# solar_harvester.net
KiCad netlist of a schematic drawn in EAGLE
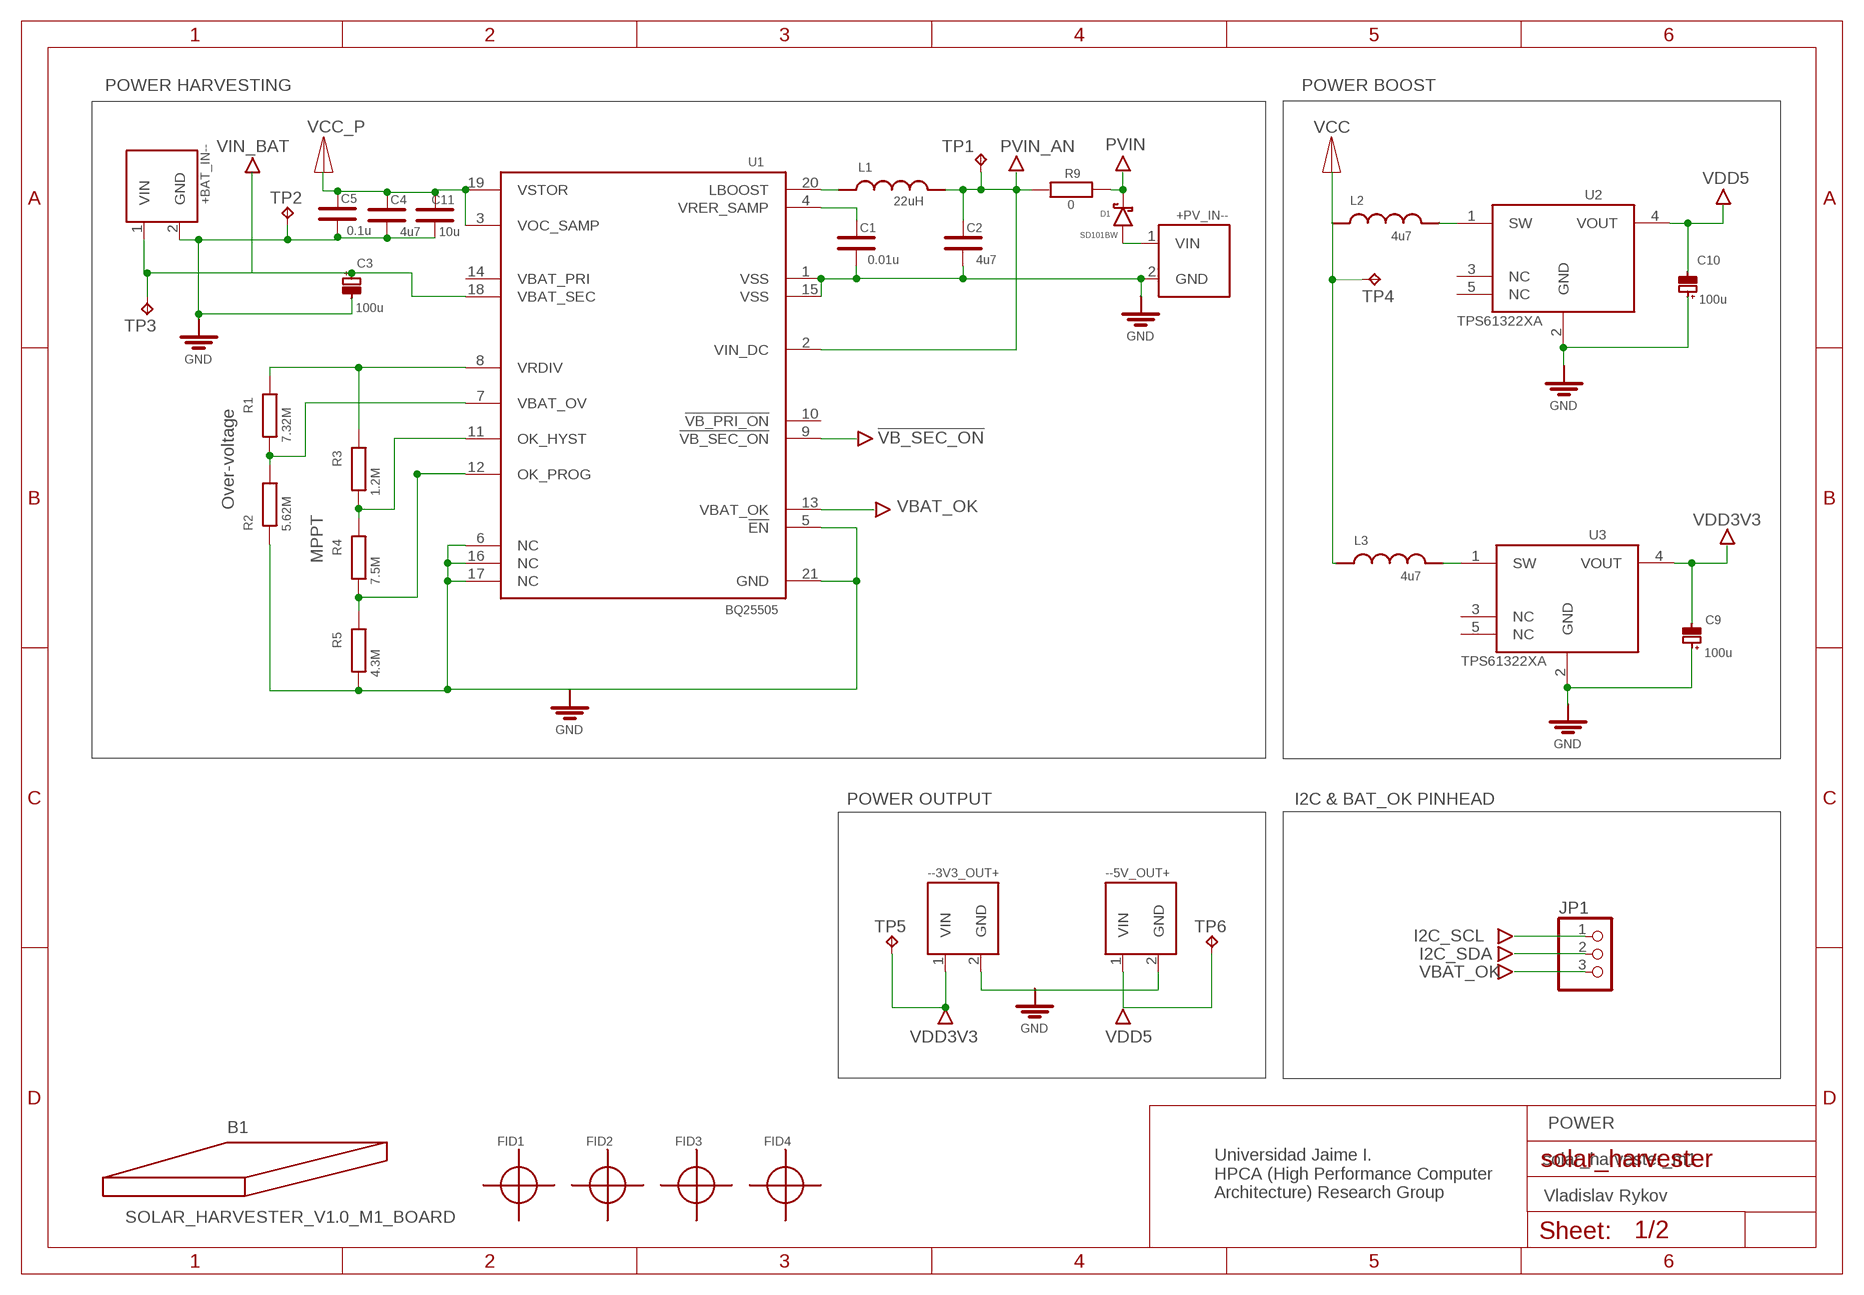
[diagram p0: schematic, sheet 1]
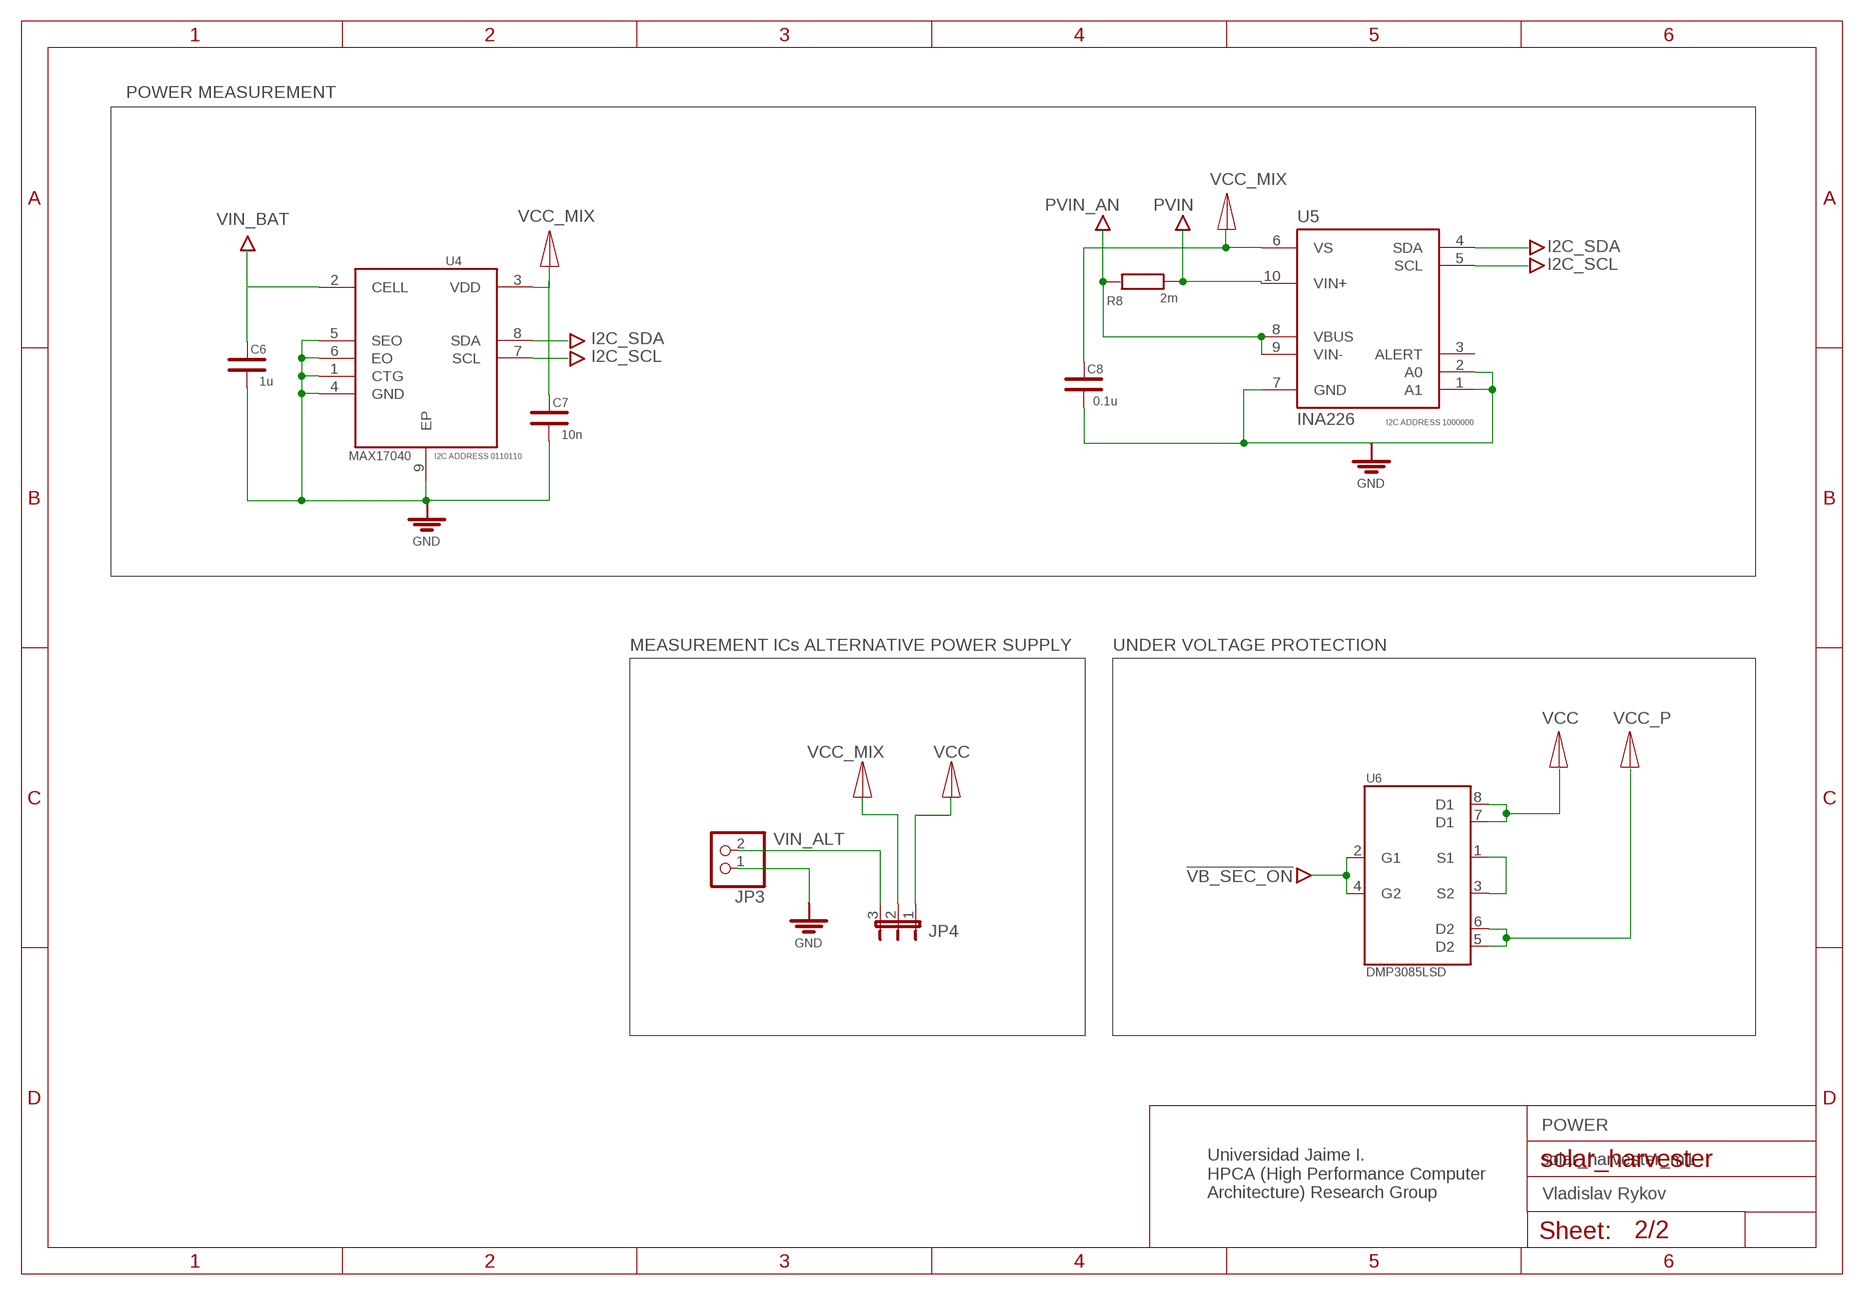
[diagram p1: schematic, sheet 2]

(export (version "E")
  (design (tool "Eeschema 10.0.6"))
  (components
    (comp (ref "C6")
      (value "1u")
      (footprint "eagle-import:1608_FOOTPRINT")
      (libsource (lib "eagle-import") (part "1608_CAP"))
    )
    (comp (ref "C7")
      (value "10n")
      (footprint "eagle-import:1608_FOOTPRINT")
      (libsource (lib "eagle-import") (part "1608_CAP"))
    )
    (comp (ref "C8")
      (value "0.1u")
      (footprint "eagle-import:1608_FOOTPRINT")
      (libsource (lib "eagle-import") (part "1608_CAP"))
    )
    (comp (ref "JP3")
      (value "PINHD-1X2")
      (footprint "eagle-import:1X02")
      (libsource (lib "eagle-import") (part "PINHD-1X2"))
    )
    (comp (ref "JP4")
      (value "JP2E")
      (footprint "eagle-import:JP2")
      (libsource (lib "eagle-import") (part "JP2E"))
    )
    (comp (ref "R8")
      (value "2m")
      (footprint "eagle-import:RESISTOR_2012_FOOTPRINT")
      (libsource (lib "eagle-import") (part "RESISTOR_2012"))
    )
    (comp (ref "U4")
      (value "MAX17040")
      (footprint "eagle-import:MAX17040G+T_FOOTPRINT")
      (libsource (lib "eagle-import") (part "MAX17040"))
    )
    (comp (ref "U5")
      (value "INA226")
      (footprint "eagle-import:INA226_FOOTPRINT")
      (libsource (lib "eagle-import") (part "INA226"))
    )
    (comp (ref "U6")
      (value "DMP3085LSD")
      (footprint "eagle-import:SO-8")
      (libsource (lib "eagle-import") (part "DMP3085LSD"))
    )
    (comp (ref "+BAT_IN--")
      (value "CONN_SCEW_TYPE_2P")
      (footprint "eagle-import:CONN_SCREW_TYPE_2P")
      (libsource (lib "eagle-import") (part "CONN_SCEW_TYPE_2P"))
    )
    (comp (ref "+PV_IN--")
      (value "CONN_SCEW_TYPE_2P")
      (footprint "eagle-import:CONN_SCREW_TYPE_2P")
      (libsource (lib "eagle-import") (part "CONN_SCEW_TYPE_2P"))
    )
    (comp (ref "--3V3_OUT+")
      (value "CONN_SCEW_TYPE_2P")
      (footprint "eagle-import:CONN_SCREW_TYPE_2P")
      (libsource (lib "eagle-import") (part "CONN_SCEW_TYPE_2P"))
    )
    (comp (ref "--5V_OUT+")
      (value "CONN_SCEW_TYPE_2P")
      (footprint "eagle-import:CONN_SCREW_TYPE_2P")
      (libsource (lib "eagle-import") (part "CONN_SCEW_TYPE_2P"))
    )
    (comp (ref "B1")
      (value "SOLAR_HARVESTER_V1.0_M1_BOARD")
      (footprint "eagle-import:SOLAR_HARVESTER_V1.0_M1_FOOTPRINT")
      (libsource (lib "eagle-import") (part "SOLAR_HARVESTER_V1.0_M1_BOARD"))
    )
    (comp (ref "C1")
      (value "0.01u")
      (footprint "eagle-import:1608_FOOTPRINT")
      (libsource (lib "eagle-import") (part "1608_CAP"))
    )
    (comp (ref "C2")
      (value "4u7")
      (footprint "eagle-import:1608_FOOTPRINT")
      (libsource (lib "eagle-import") (part "1608_CAP"))
    )
    (comp (ref "C3")
      (value "100u")
      (footprint "eagle-import:3528_TAN_FOOTPRINT")
      (libsource (lib "eagle-import") (part "3528_POL_CAP"))
    )
    (comp (ref "C4")
      (value "4u7")
      (footprint "eagle-import:1608_FOOTPRINT")
      (libsource (lib "eagle-import") (part "1608_CAP"))
    )
    (comp (ref "C5")
      (value "0.1u")
      (footprint "eagle-import:1608_FOOTPRINT")
      (libsource (lib "eagle-import") (part "1608_CAP"))
    )
    (comp (ref "C9")
      (value "100u")
      (footprint "eagle-import:3528_TAN_FOOTPRINT")
      (libsource (lib "eagle-import") (part "3528_POL_CAP"))
    )
    (comp (ref "C10")
      (value "100u")
      (footprint "eagle-import:3528_TAN_FOOTPRINT")
      (libsource (lib "eagle-import") (part "3528_POL_CAP"))
    )
    (comp (ref "C11")
      (value "10u")
      (footprint "eagle-import:1608_FOOTPRINT")
      (libsource (lib "eagle-import") (part "1608_CAP"))
    )
    (comp (ref "D1")
      (value "SD101BW")
      (footprint "eagle-import:SOD-123")
      (libsource (lib "eagle-import") (part "SD101BW"))
    )
    (comp (ref "FID1")
      (value "FIDUCIAL_25")
      (footprint "eagle-import:FIDUCIAL_25")
      (libsource (lib "eagle-import") (part "FIDUCIAL_25"))
    )
    (comp (ref "FID2")
      (value "FIDUCIAL_25")
      (footprint "eagle-import:FIDUCIAL_25")
      (libsource (lib "eagle-import") (part "FIDUCIAL_25"))
    )
    (comp (ref "FID3")
      (value "FIDUCIAL_25")
      (footprint "eagle-import:FIDUCIAL_25")
      (libsource (lib "eagle-import") (part "FIDUCIAL_25"))
    )
    (comp (ref "FID4")
      (value "FIDUCIAL_25")
      (footprint "eagle-import:FIDUCIAL_25")
      (libsource (lib "eagle-import") (part "FIDUCIAL_25"))
    )
    (comp (ref "JP1")
      (value "PINHD-1X3")
      (footprint "eagle-import:1X03")
      (libsource (lib "eagle-import") (part "PINHD-1X3"))
    )
    (comp (ref "L1")
      (value "22uH")
      (footprint "eagle-import:FIXED_4040_FOOTPRINT")
      (libsource (lib "eagle-import") (part "FIXED_4040"))
    )
    (comp (ref "L2")
      (value "4u7")
      (footprint "eagle-import:FIXED_5050_FOOTPRINT")
      (libsource (lib "eagle-import") (part "FIXED_5050"))
    )
    (comp (ref "L3")
      (value "4u7")
      (footprint "eagle-import:FIXED_2520_FOOTPRINT")
      (libsource (lib "eagle-import") (part "FIXED_2520"))
    )
    (comp (ref "R1")
      (value "7.32M")
      (footprint "eagle-import:RESISTOR_1608_FOOTPRINT")
      (libsource (lib "eagle-import") (part "RESISTOR_1608"))
    )
    (comp (ref "R2")
      (value "5.62M")
      (footprint "eagle-import:RESISTOR_1608_FOOTPRINT")
      (libsource (lib "eagle-import") (part "RESISTOR_1608"))
    )
    (comp (ref "R3")
      (value "1.2M")
      (footprint "eagle-import:RESISTOR_1608_FOOTPRINT")
      (libsource (lib "eagle-import") (part "RESISTOR_1608"))
    )
    (comp (ref "R4")
      (value "7.5M")
      (footprint "eagle-import:RESISTOR_1608_FOOTPRINT")
      (libsource (lib "eagle-import") (part "RESISTOR_1608"))
    )
    (comp (ref "R5")
      (value "4.3M")
      (footprint "eagle-import:RESISTOR_1608_FOOTPRINT")
      (libsource (lib "eagle-import") (part "RESISTOR_1608"))
    )
    (comp (ref "R9")
      (value "0")
      (footprint "eagle-import:RESISTOR_1608_FOOTPRINT")
      (libsource (lib "eagle-import") (part "RESISTOR_1608"))
    )
    (comp (ref "TP1")
      (value "TPTP10SQ")
      (footprint "eagle-import:TP10SQ")
      (libsource (lib "eagle-import") (part "TPTP10SQ"))
    )
    (comp (ref "TP2")
      (value "TPTP10SQ")
      (footprint "eagle-import:TP10SQ")
      (libsource (lib "eagle-import") (part "TPTP10SQ"))
    )
    (comp (ref "TP3")
      (value "TPTP10SQ")
      (footprint "eagle-import:TP10SQ")
      (libsource (lib "eagle-import") (part "TPTP10SQ"))
    )
    (comp (ref "TP4")
      (value "TPTP10SQ")
      (footprint "eagle-import:TP10SQ")
      (libsource (lib "eagle-import") (part "TPTP10SQ"))
    )
    (comp (ref "TP5")
      (value "TPTP10SQ")
      (footprint "eagle-import:TP10SQ")
      (libsource (lib "eagle-import") (part "TPTP10SQ"))
    )
    (comp (ref "TP6")
      (value "TPTP10SQ")
      (footprint "eagle-import:TP10SQ")
      (libsource (lib "eagle-import") (part "TPTP10SQ"))
    )
    (comp (ref "U1")
      (value "BQ25505")
      (footprint "eagle-import:BQ25505_FOOTPRINT")
      (libsource (lib "eagle-import") (part "BQ25505"))
    )
    (comp (ref "U2")
      (value "TPS61322XA")
      (footprint "eagle-import:TPS61322XA_FOOTPRINT")
      (libsource (lib "eagle-import") (part "TPS61322XA"))
    )
    (comp (ref "U3")
      (value "TPS61322XA")
      (footprint "eagle-import:TPS61322XA_FOOTPRINT")
      (libsource (lib "eagle-import") (part "TPS61322XA"))
    )
  )
  (nets
    (net (code "1") (name "GND") (class "Default")
      (node (ref "+BAT_IN--") (pin "2") (pinfunction "GND_2") (pintype "bidirectional"))
      (node (ref "+PV_IN--") (pin "2") (pinfunction "GND_2") (pintype "bidirectional"))
      (node (ref "--3V3_OUT+") (pin "2") (pinfunction "GND_2") (pintype "bidirectional"))
      (node (ref "--5V_OUT+") (pin "2") (pinfunction "GND_2") (pintype "bidirectional"))
      (node (ref "C1") (pin "2") (pinfunction "2_2") (pintype "bidirectional"))
      (node (ref "C10") (pin "1") (pinfunction "1_1") (pintype "bidirectional"))
      (node (ref "C11") (pin "2") (pinfunction "2_2") (pintype "bidirectional"))
      (node (ref "C2") (pin "2") (pinfunction "2_2") (pintype "bidirectional"))
      (node (ref "C3") (pin "2") (pinfunction "2_2") (pintype "bidirectional"))
      (node (ref "C4") (pin "2") (pinfunction "2_2") (pintype "bidirectional"))
      (node (ref "C5") (pin "2") (pinfunction "2_2") (pintype "bidirectional"))
      (node (ref "C6") (pin "2") (pinfunction "2_2") (pintype "bidirectional"))
      (node (ref "C7") (pin "2") (pinfunction "2_2") (pintype "bidirectional"))
      (node (ref "C8") (pin "2") (pinfunction "2_2") (pintype "bidirectional"))
      (node (ref "C9") (pin "1") (pinfunction "1_1") (pintype "bidirectional"))
      (node (ref "JP3") (pin "1") (pinfunction "1_1") (pintype "passive"))
      (node (ref "R2") (pin "1") (pinfunction "P$1_1") (pintype "bidirectional"))
      (node (ref "R5") (pin "1") (pinfunction "P$1_1") (pintype "bidirectional"))
      (node (ref "TP2") (pin "TP") (pinfunction "TP_TP") (pintype "input"))
      (node (ref "U1") (pin "1") (pinfunction "VSS_1") (pintype "bidirectional"))
      (node (ref "U1") (pin "15") (pinfunction "VSS_15") (pintype "bidirectional"))
      (node (ref "U1") (pin "16") (pinfunction "NC_16") (pintype "bidirectional"))
      (node (ref "U1") (pin "17") (pinfunction "NC_17") (pintype "bidirectional"))
      (node (ref "U1") (pin "21") (pinfunction "GND_21") (pintype "bidirectional"))
      (node (ref "U1") (pin "5") (pinfunction "~{EN}_5") (pintype "bidirectional"))
      (node (ref "U1") (pin "6") (pinfunction "NC_6") (pintype "bidirectional"))
      (node (ref "U2") (pin "2") (pinfunction "GND_2") (pintype "bidirectional"))
      (node (ref "U3") (pin "2") (pinfunction "GND_2") (pintype "bidirectional"))
      (node (ref "U4") (pin "1") (pinfunction "CTG_1") (pintype "bidirectional"))
      (node (ref "U4") (pin "4") (pinfunction "GND_4") (pintype "bidirectional"))
      (node (ref "U4") (pin "5") (pinfunction "SEO_5") (pintype "bidirectional"))
      (node (ref "U4") (pin "6") (pinfunction "EO_6") (pintype "bidirectional"))
      (node (ref "U4") (pin "9") (pinfunction "EP_9") (pintype "bidirectional"))
      (node (ref "U5") (pin "1") (pinfunction "A1_1") (pintype "bidirectional"))
      (node (ref "U5") (pin "2") (pinfunction "A0_2") (pintype "bidirectional"))
      (node (ref "U5") (pin "7") (pinfunction "GND_7") (pintype "bidirectional"))
    )
    (net (code "2") (name "I2C_SCL") (class "Default")
      (node (ref "JP1") (pin "1") (pinfunction "1_1") (pintype "passive"))
      (node (ref "U4") (pin "7") (pinfunction "SCL_7") (pintype "bidirectional"))
      (node (ref "U5") (pin "5") (pinfunction "SCL_5") (pintype "bidirectional"))
    )
    (net (code "3") (name "I2C_SDA") (class "Default")
      (node (ref "JP1") (pin "2") (pinfunction "2_2") (pintype "passive"))
      (node (ref "U4") (pin "8") (pinfunction "SDA_8") (pintype "bidirectional"))
      (node (ref "U5") (pin "4") (pinfunction "SDA_4") (pintype "bidirectional"))
    )
    (net (code "4") (name "Net-(+PV_IN---VIN)") (class "Default")
      (node (ref "+PV_IN--") (pin "1") (pinfunction "VIN_1") (pintype "bidirectional"))
      (node (ref "D1") (pin "2") (pinfunction "2_2") (pintype "bidirectional"))
    )
    (net (code "5") (name "Net-(R1-P$1)") (class "Default")
      (node (ref "R1") (pin "1") (pinfunction "P$1_1") (pintype "bidirectional"))
      (node (ref "R2") (pin "2") (pinfunction "P$2_2") (pintype "bidirectional"))
      (node (ref "U1") (pin "7") (pinfunction "VBAT_OV_7") (pintype "bidirectional"))
    )
    (net (code "6") (name "Net-(R1-P$2)") (class "Default")
      (node (ref "R1") (pin "2") (pinfunction "P$2_2") (pintype "bidirectional"))
      (node (ref "R3") (pin "2") (pinfunction "P$2_2") (pintype "bidirectional"))
      (node (ref "U1") (pin "8") (pinfunction "VRDIV_8") (pintype "bidirectional"))
    )
    (net (code "7") (name "Net-(R3-P$1)") (class "Default")
      (node (ref "R3") (pin "1") (pinfunction "P$1_1") (pintype "bidirectional"))
      (node (ref "R4") (pin "2") (pinfunction "P$2_2") (pintype "bidirectional"))
      (node (ref "U1") (pin "11") (pinfunction "OK_HYST_11") (pintype "bidirectional"))
    )
    (net (code "8") (name "Net-(R4-P$1)") (class "Default")
      (node (ref "R4") (pin "1") (pinfunction "P$1_1") (pintype "bidirectional"))
      (node (ref "R5") (pin "2") (pinfunction "P$2_2") (pintype "bidirectional"))
      (node (ref "U1") (pin "12") (pinfunction "OK_PROG_12") (pintype "bidirectional"))
    )
    (net (code "9") (name "Net-(U1-LBOOST)") (class "Default")
      (node (ref "L1") (pin "1") (pinfunction "1_1") (pintype "bidirectional"))
      (node (ref "U1") (pin "20") (pinfunction "LBOOST_20") (pintype "bidirectional"))
    )
    (net (code "10") (name "Net-(U1-VRER_SAMP)") (class "Default")
      (node (ref "C1") (pin "1") (pinfunction "1_1") (pintype "bidirectional"))
      (node (ref "U1") (pin "4") (pinfunction "VRER_SAMP_4") (pintype "bidirectional"))
    )
    (net (code "11") (name "Net-(U2-SW)") (class "Default")
      (node (ref "L2") (pin "2") (pinfunction "2_2") (pintype "bidirectional"))
      (node (ref "U2") (pin "1") (pinfunction "SW_1") (pintype "bidirectional"))
    )
    (net (code "12") (name "Net-(U3-SW)") (class "Default")
      (node (ref "L3") (pin "2") (pinfunction "2_2") (pintype "bidirectional"))
      (node (ref "U3") (pin "1") (pinfunction "SW_1") (pintype "bidirectional"))
    )
    (net (code "13") (name "Net-(U6-S1)") (class "Default")
      (node (ref "U6") (pin "1") (pinfunction "S1_1") (pintype "bidirectional"))
      (node (ref "U6") (pin "3") (pinfunction "S2_3") (pintype "bidirectional"))
    )
    (net (code "14") (name "PVIN") (class "Default")
      (node (ref "D1") (pin "1") (pinfunction "1_1") (pintype "bidirectional"))
      (node (ref "R8") (pin "2") (pinfunction "P$2_2") (pintype "bidirectional"))
      (node (ref "R9") (pin "2") (pinfunction "P$2_2") (pintype "bidirectional"))
      (node (ref "U5") (pin "10") (pinfunction "VIN+_10") (pintype "bidirectional"))
    )
    (net (code "15") (name "PVIN_AN") (class "Default")
      (node (ref "C2") (pin "1") (pinfunction "1_1") (pintype "bidirectional"))
      (node (ref "L1") (pin "2") (pinfunction "2_2") (pintype "bidirectional"))
      (node (ref "R8") (pin "1") (pinfunction "P$1_1") (pintype "bidirectional"))
      (node (ref "R9") (pin "1") (pinfunction "P$1_1") (pintype "bidirectional"))
      (node (ref "TP1") (pin "TP") (pinfunction "TP_TP") (pintype "input"))
      (node (ref "U1") (pin "2") (pinfunction "VIN_DC_2") (pintype "bidirectional"))
      (node (ref "U5") (pin "8") (pinfunction "VBUS_8") (pintype "bidirectional"))
      (node (ref "U5") (pin "9") (pinfunction "VIN-_9") (pintype "bidirectional"))
    )
    (net (code "16") (name "VBAT_OK") (class "Default")
      (node (ref "JP1") (pin "3") (pinfunction "3_3") (pintype "passive"))
      (node (ref "U1") (pin "13") (pinfunction "VBAT_OK_13") (pintype "bidirectional"))
    )
    (net (code "17") (name "VCC") (class "Default")
      (node (ref "JP4") (pin "1") (pinfunction "1_1") (pintype "passive"))
      (node (ref "L2") (pin "1") (pinfunction "1_1") (pintype "bidirectional"))
      (node (ref "L3") (pin "1") (pinfunction "1_1") (pintype "bidirectional"))
      (node (ref "TP4") (pin "TP") (pinfunction "TP_TP") (pintype "input"))
      (node (ref "U6") (pin "7") (pinfunction "D1_7") (pintype "bidirectional"))
      (node (ref "U6") (pin "8") (pinfunction "D1_8") (pintype "bidirectional"))
    )
    (net (code "18") (name "VCC_MIX") (class "Default")
      (node (ref "C7") (pin "1") (pinfunction "1_1") (pintype "bidirectional"))
      (node (ref "C8") (pin "1") (pinfunction "1_1") (pintype "bidirectional"))
      (node (ref "JP4") (pin "2") (pinfunction "2_2") (pintype "passive"))
      (node (ref "U4") (pin "3") (pinfunction "VDD_3") (pintype "bidirectional"))
      (node (ref "U5") (pin "6") (pinfunction "VS_6") (pintype "bidirectional"))
    )
    (net (code "19") (name "VCC_P") (class "Default")
      (node (ref "C11") (pin "1") (pinfunction "1_1") (pintype "bidirectional"))
      (node (ref "C4") (pin "1") (pinfunction "1_1") (pintype "bidirectional"))
      (node (ref "C5") (pin "1") (pinfunction "1_1") (pintype "bidirectional"))
      (node (ref "U1") (pin "19") (pinfunction "VSTOR_19") (pintype "bidirectional"))
      (node (ref "U1") (pin "3") (pinfunction "VOC_SAMP_3") (pintype "bidirectional"))
      (node (ref "U6") (pin "5") (pinfunction "D2_5") (pintype "bidirectional"))
      (node (ref "U6") (pin "6") (pinfunction "D2_6") (pintype "bidirectional"))
    )
    (net (code "20") (name "VDD3V3") (class "Default")
      (node (ref "--3V3_OUT+") (pin "1") (pinfunction "VIN_1") (pintype "bidirectional"))
      (node (ref "C9") (pin "2") (pinfunction "2_2") (pintype "bidirectional"))
      (node (ref "TP5") (pin "TP") (pinfunction "TP_TP") (pintype "input"))
      (node (ref "U3") (pin "4") (pinfunction "VOUT_4") (pintype "bidirectional"))
    )
    (net (code "21") (name "VDD5") (class "Default")
      (node (ref "--5V_OUT+") (pin "1") (pinfunction "VIN_1") (pintype "bidirectional"))
      (node (ref "C10") (pin "2") (pinfunction "2_2") (pintype "bidirectional"))
      (node (ref "TP6") (pin "TP") (pinfunction "TP_TP") (pintype "input"))
      (node (ref "U2") (pin "4") (pinfunction "VOUT_4") (pintype "bidirectional"))
    )
    (net (code "22") (name "VIN_ALT") (class "Default")
      (node (ref "JP3") (pin "2") (pinfunction "2_2") (pintype "passive"))
      (node (ref "JP4") (pin "3") (pinfunction "3_3") (pintype "passive"))
    )
    (net (code "23") (name "VIN_BAT") (class "Default")
      (node (ref "+BAT_IN--") (pin "1") (pinfunction "VIN_1") (pintype "bidirectional"))
      (node (ref "C3") (pin "1") (pinfunction "1_1") (pintype "bidirectional"))
      (node (ref "C6") (pin "1") (pinfunction "1_1") (pintype "bidirectional"))
      (node (ref "TP3") (pin "TP") (pinfunction "TP_TP") (pintype "input"))
      (node (ref "U1") (pin "18") (pinfunction "VBAT_SEC_18") (pintype "bidirectional"))
      (node (ref "U4") (pin "2") (pinfunction "CELL_2") (pintype "bidirectional"))
    )
    (net (code "24") (name "unconnected-(U1-VBAT_PRI-Pad14)") (class "Default")
      (node (ref "U1") (pin "14") (pinfunction "VBAT_PRI_14") (pintype "bidirectional"))
    )
    (net (code "25") (name "unconnected-(U1-~{VB_PRI_ON}-Pad10)") (class "Default")
      (node (ref "U1") (pin "10") (pinfunction "~{VB_PRI_ON}_10") (pintype "bidirectional"))
    )
    (net (code "26") (name "unconnected-(U2-NC-Pad3)") (class "Default")
      (node (ref "U2") (pin "3") (pinfunction "NC_3") (pintype "bidirectional"))
    )
    (net (code "27") (name "unconnected-(U2-NC-Pad5)") (class "Default")
      (node (ref "U2") (pin "5") (pinfunction "NC_5") (pintype "bidirectional"))
    )
    (net (code "28") (name "unconnected-(U3-NC-Pad3)") (class "Default")
      (node (ref "U3") (pin "3") (pinfunction "NC_3") (pintype "bidirectional"))
    )
    (net (code "29") (name "unconnected-(U3-NC-Pad5)") (class "Default")
      (node (ref "U3") (pin "5") (pinfunction "NC_5") (pintype "bidirectional"))
    )
    (net (code "30") (name "unconnected-(U5-ALERT-Pad3)") (class "Default")
      (node (ref "U5") (pin "3") (pinfunction "ALERT_3") (pintype "bidirectional"))
    )
    (net (code "31") (name "~{VB_SEC_ON}") (class "Default")
      (node (ref "U1") (pin "9") (pinfunction "~{VB_SEC_ON}_9") (pintype "bidirectional"))
      (node (ref "U6") (pin "2") (pinfunction "G1_2") (pintype "bidirectional"))
      (node (ref "U6") (pin "4") (pinfunction "G2_4") (pintype "bidirectional"))
    )
  )
)
